# M203X.net
KiCad netlist of a schematic drawn in EAGLE
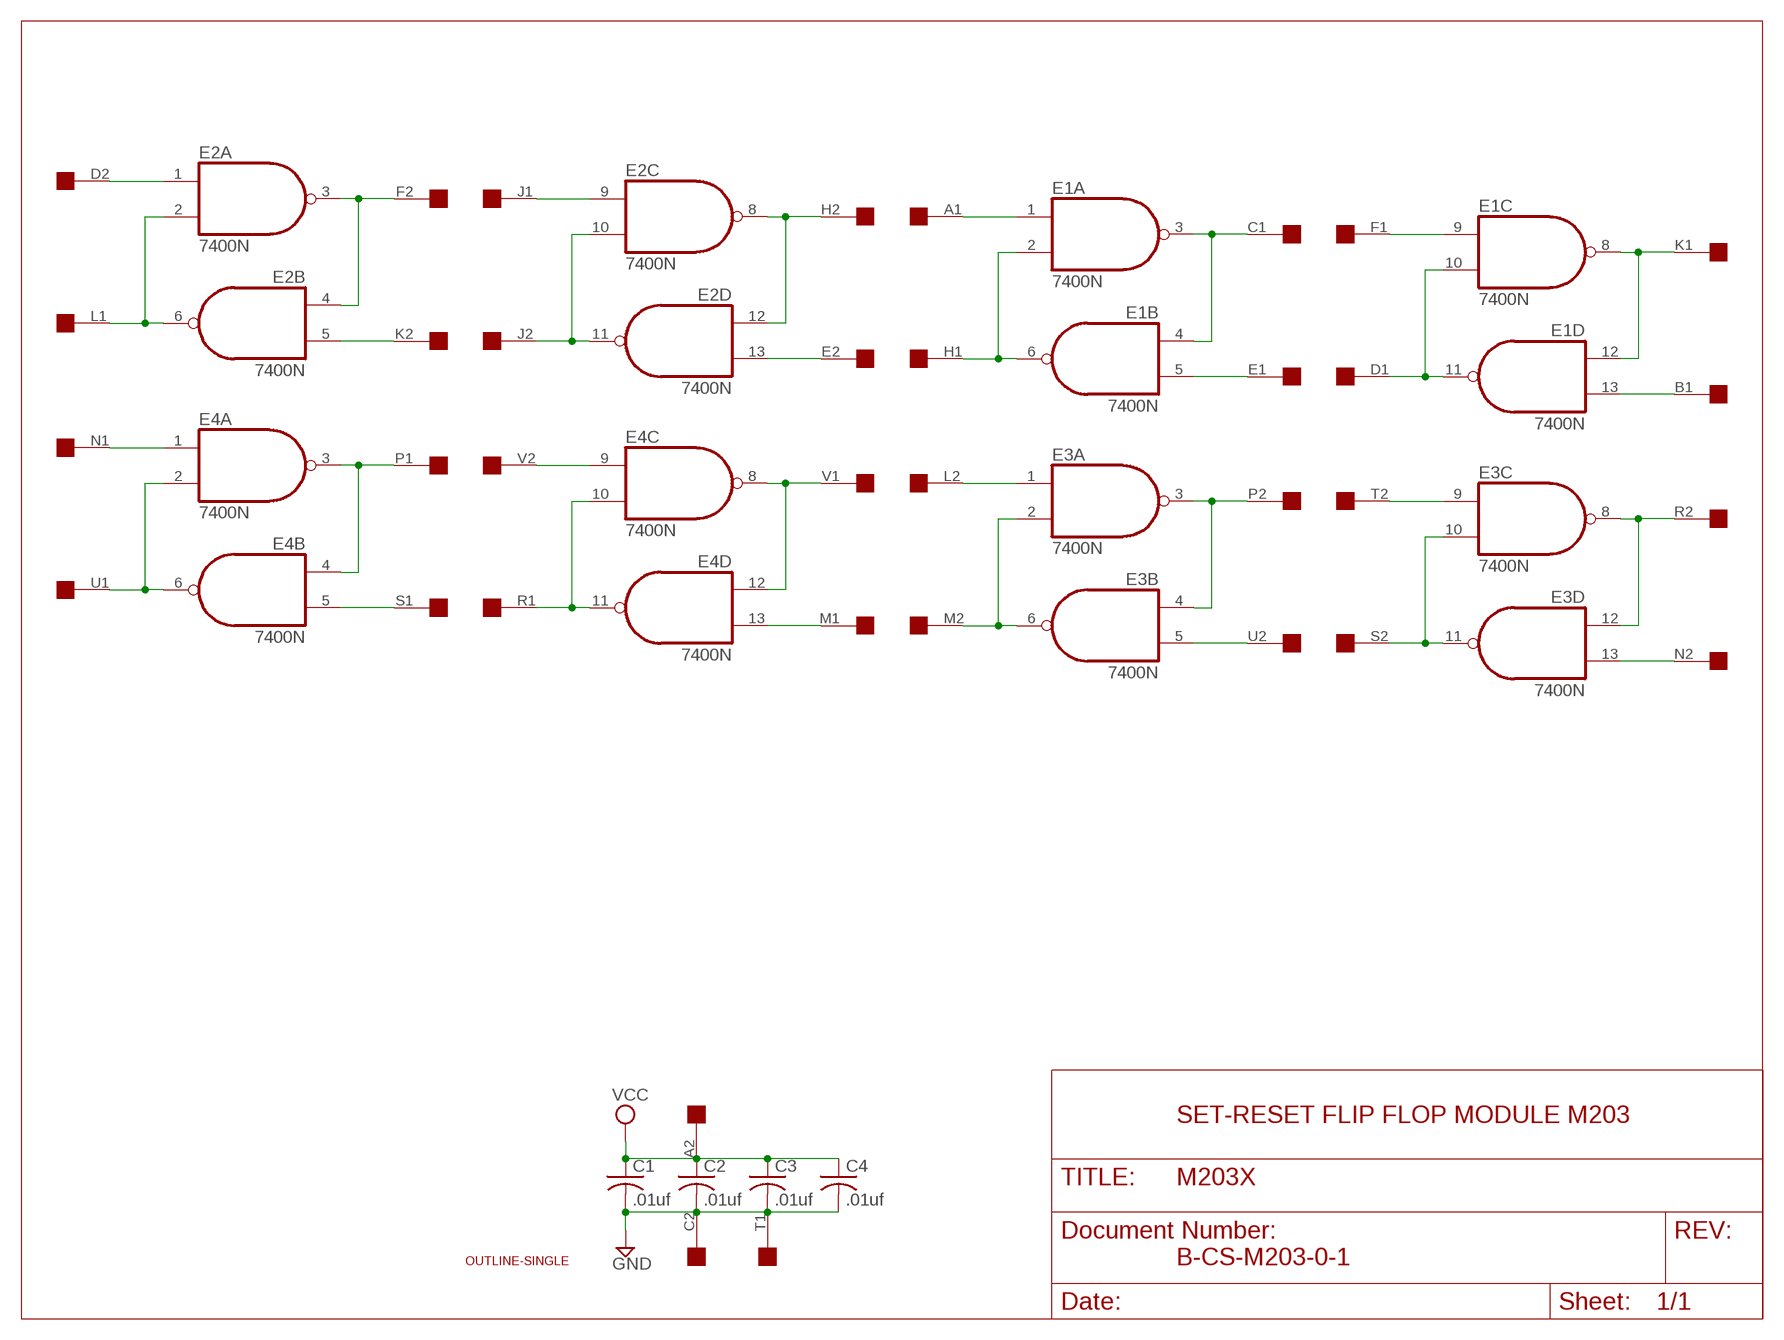
[diagram p0: schematic, sheet 1]

(export (version "E")
  (design (tool "Eeschema 10.0.6"))
  (components
    (comp (ref "C1")
      (value ".01uf")
      (footprint "eagle-import:C050-025X075")
      (libsource (lib "eagle-import") (part "C-US050-025X075"))
    )
    (comp (ref "C2")
      (value ".01uf")
      (footprint "eagle-import:C050-025X075")
      (libsource (lib "eagle-import") (part "C-US050-025X075"))
    )
    (comp (ref "C3")
      (value ".01uf")
      (footprint "eagle-import:C050-025X075")
      (libsource (lib "eagle-import") (part "C-US050-025X075"))
    )
    (comp (ref "C4")
      (value ".01uf")
      (footprint "eagle-import:C050-025X075")
      (libsource (lib "eagle-import") (part "C-US050-025X075"))
    )
    (comp (ref "E1")
      (value "7400N")
      (footprint "eagle-import:DIL14")
      (libsource (lib "eagle-import") (part "7400N"))
    )
    (comp (ref "E2")
      (value "7400N")
      (footprint "eagle-import:DIL14")
      (libsource (lib "eagle-import") (part "7400N"))
    )
    (comp (ref "E3")
      (value "7400N")
      (footprint "eagle-import:DIL14")
      (libsource (lib "eagle-import") (part "7400N"))
    )
    (comp (ref "E4")
      (value "7400N")
      (footprint "eagle-import:DIL14")
      (libsource (lib "eagle-import") (part "7400N"))
    )
    (comp (ref "U$1")
      (value "OUTLINE-SINGLE")
      (footprint "eagle-import:SINGLE")
      (libsource (lib "eagle-import") (part "OUTLINE-SINGLE"))
    )
    (comp (ref "U$2")
      (value "EDGE-2CONNECTOR")
      (footprint "eagle-import:EDGE-CON2")
      (libsource (lib "eagle-import") (part "EDGE-2CONNECTOR"))
    )
  )
  (nets
    (net (code "1") (name "GND") (class "Default")
      (node (ref "C1") (pin "2") (pinfunction "2_2") (pintype "passive"))
      (node (ref "C2") (pin "2") (pinfunction "2_2") (pintype "passive"))
      (node (ref "C3") (pin "2") (pinfunction "2_2") (pintype "passive"))
      (node (ref "C4") (pin "2") (pinfunction "2_2") (pintype "passive"))
      (node (ref "U$2") (pin "C2") (pinfunction "1_C2") (pintype "bidirectional"))
      (node (ref "U$2") (pin "T1") (pinfunction "1_T1") (pintype "bidirectional"))
    )
    (net (code "2") (name "Net-(E1A-I0)") (class "Default")
      (node (ref "E1") (pin "1") (pinfunction "I0_1") (pintype "input"))
      (node (ref "U$2") (pin "A1") (pinfunction "1_A1") (pintype "bidirectional"))
    )
    (net (code "3") (name "Net-(E1A-I1)") (class "Default")
      (node (ref "E1") (pin "2") (pinfunction "I1_2") (pintype "input"))
      (node (ref "E1") (pin "6") (pinfunction "O_6") (pintype "output"))
      (node (ref "U$2") (pin "H1") (pinfunction "1_H1") (pintype "bidirectional"))
    )
    (net (code "4") (name "Net-(E1A-O)") (class "Default")
      (node (ref "E1") (pin "3") (pinfunction "O_3") (pintype "output"))
      (node (ref "E1") (pin "4") (pinfunction "I0_4") (pintype "input"))
      (node (ref "U$2") (pin "C1") (pinfunction "1_C1") (pintype "bidirectional"))
    )
    (net (code "5") (name "Net-(E1B-I1)") (class "Default")
      (node (ref "E1") (pin "5") (pinfunction "I1_5") (pintype "input"))
      (node (ref "U$2") (pin "E1") (pinfunction "1_E1") (pintype "bidirectional"))
    )
    (net (code "6") (name "Net-(E1C-I0)") (class "Default")
      (node (ref "E1") (pin "9") (pinfunction "I0_9") (pintype "input"))
      (node (ref "U$2") (pin "F1") (pinfunction "1_F1") (pintype "bidirectional"))
    )
    (net (code "7") (name "Net-(E1C-I1)") (class "Default")
      (node (ref "E1") (pin "10") (pinfunction "I1_10") (pintype "input"))
      (node (ref "E1") (pin "11") (pinfunction "O_11") (pintype "output"))
      (node (ref "U$2") (pin "D1") (pinfunction "1_D1") (pintype "bidirectional"))
    )
    (net (code "8") (name "Net-(E1C-O)") (class "Default")
      (node (ref "E1") (pin "12") (pinfunction "I0_12") (pintype "input"))
      (node (ref "E1") (pin "8") (pinfunction "O_8") (pintype "output"))
      (node (ref "U$2") (pin "K1") (pinfunction "1_K1") (pintype "bidirectional"))
    )
    (net (code "9") (name "Net-(E1D-I1)") (class "Default")
      (node (ref "E1") (pin "13") (pinfunction "I1_13") (pintype "input"))
      (node (ref "U$2") (pin "B1") (pinfunction "1_B1") (pintype "bidirectional"))
    )
    (net (code "10") (name "Net-(E2A-I0)") (class "Default")
      (node (ref "E2") (pin "1") (pinfunction "I0_1") (pintype "input"))
      (node (ref "U$2") (pin "D2") (pinfunction "1_D2") (pintype "bidirectional"))
    )
    (net (code "11") (name "Net-(E2A-I1)") (class "Default")
      (node (ref "E2") (pin "2") (pinfunction "I1_2") (pintype "input"))
      (node (ref "E2") (pin "6") (pinfunction "O_6") (pintype "output"))
      (node (ref "U$2") (pin "L1") (pinfunction "1_L1") (pintype "bidirectional"))
    )
    (net (code "12") (name "Net-(E2A-O)") (class "Default")
      (node (ref "E2") (pin "3") (pinfunction "O_3") (pintype "output"))
      (node (ref "E2") (pin "4") (pinfunction "I0_4") (pintype "input"))
      (node (ref "U$2") (pin "F2") (pinfunction "1_F2") (pintype "bidirectional"))
    )
    (net (code "13") (name "Net-(E2B-I1)") (class "Default")
      (node (ref "E2") (pin "5") (pinfunction "I1_5") (pintype "input"))
      (node (ref "U$2") (pin "K2") (pinfunction "1_K2") (pintype "bidirectional"))
    )
    (net (code "14") (name "Net-(E2C-I0)") (class "Default")
      (node (ref "E2") (pin "9") (pinfunction "I0_9") (pintype "input"))
      (node (ref "U$2") (pin "J1") (pinfunction "1_J1") (pintype "bidirectional"))
    )
    (net (code "15") (name "Net-(E2C-I1)") (class "Default")
      (node (ref "E2") (pin "10") (pinfunction "I1_10") (pintype "input"))
      (node (ref "E2") (pin "11") (pinfunction "O_11") (pintype "output"))
      (node (ref "U$2") (pin "J2") (pinfunction "1_J2") (pintype "bidirectional"))
    )
    (net (code "16") (name "Net-(E2C-O)") (class "Default")
      (node (ref "E2") (pin "12") (pinfunction "I0_12") (pintype "input"))
      (node (ref "E2") (pin "8") (pinfunction "O_8") (pintype "output"))
      (node (ref "U$2") (pin "H2") (pinfunction "1_H2") (pintype "bidirectional"))
    )
    (net (code "17") (name "Net-(E2D-I1)") (class "Default")
      (node (ref "E2") (pin "13") (pinfunction "I1_13") (pintype "input"))
      (node (ref "U$2") (pin "E2") (pinfunction "1_E2") (pintype "bidirectional"))
    )
    (net (code "18") (name "Net-(E3A-I0)") (class "Default")
      (node (ref "E3") (pin "1") (pinfunction "I0_1") (pintype "input"))
      (node (ref "U$2") (pin "L2") (pinfunction "1_L2") (pintype "bidirectional"))
    )
    (net (code "19") (name "Net-(E3A-I1)") (class "Default")
      (node (ref "E3") (pin "2") (pinfunction "I1_2") (pintype "input"))
      (node (ref "E3") (pin "6") (pinfunction "O_6") (pintype "output"))
      (node (ref "U$2") (pin "M2") (pinfunction "1_M2") (pintype "bidirectional"))
    )
    (net (code "20") (name "Net-(E3A-O)") (class "Default")
      (node (ref "E3") (pin "3") (pinfunction "O_3") (pintype "output"))
      (node (ref "E3") (pin "4") (pinfunction "I0_4") (pintype "input"))
      (node (ref "U$2") (pin "P2") (pinfunction "1_P2") (pintype "bidirectional"))
    )
    (net (code "21") (name "Net-(E3B-I1)") (class "Default")
      (node (ref "E3") (pin "5") (pinfunction "I1_5") (pintype "input"))
      (node (ref "U$2") (pin "U2") (pinfunction "1_U2") (pintype "bidirectional"))
    )
    (net (code "22") (name "Net-(E3C-I0)") (class "Default")
      (node (ref "E3") (pin "9") (pinfunction "I0_9") (pintype "input"))
      (node (ref "U$2") (pin "T2") (pinfunction "1_T2") (pintype "bidirectional"))
    )
    (net (code "23") (name "Net-(E3C-I1)") (class "Default")
      (node (ref "E3") (pin "10") (pinfunction "I1_10") (pintype "input"))
      (node (ref "E3") (pin "11") (pinfunction "O_11") (pintype "output"))
      (node (ref "U$2") (pin "S2") (pinfunction "1_S2") (pintype "bidirectional"))
    )
    (net (code "24") (name "Net-(E3C-O)") (class "Default")
      (node (ref "E3") (pin "12") (pinfunction "I0_12") (pintype "input"))
      (node (ref "E3") (pin "8") (pinfunction "O_8") (pintype "output"))
      (node (ref "U$2") (pin "R2") (pinfunction "1_R2") (pintype "bidirectional"))
    )
    (net (code "25") (name "Net-(E3D-I1)") (class "Default")
      (node (ref "E3") (pin "13") (pinfunction "I1_13") (pintype "input"))
      (node (ref "U$2") (pin "N2") (pinfunction "1_N2") (pintype "bidirectional"))
    )
    (net (code "26") (name "Net-(E4A-I0)") (class "Default")
      (node (ref "E4") (pin "1") (pinfunction "I0_1") (pintype "input"))
      (node (ref "U$2") (pin "N1") (pinfunction "1_N1") (pintype "bidirectional"))
    )
    (net (code "27") (name "Net-(E4A-I1)") (class "Default")
      (node (ref "E4") (pin "2") (pinfunction "I1_2") (pintype "input"))
      (node (ref "E4") (pin "6") (pinfunction "O_6") (pintype "output"))
      (node (ref "U$2") (pin "U1") (pinfunction "1_U1") (pintype "bidirectional"))
    )
    (net (code "28") (name "Net-(E4A-O)") (class "Default")
      (node (ref "E4") (pin "3") (pinfunction "O_3") (pintype "output"))
      (node (ref "E4") (pin "4") (pinfunction "I0_4") (pintype "input"))
      (node (ref "U$2") (pin "P1") (pinfunction "1_P1") (pintype "bidirectional"))
    )
    (net (code "29") (name "Net-(E4B-I1)") (class "Default")
      (node (ref "E4") (pin "5") (pinfunction "I1_5") (pintype "input"))
      (node (ref "U$2") (pin "S1") (pinfunction "1_S1") (pintype "bidirectional"))
    )
    (net (code "30") (name "Net-(E4C-I0)") (class "Default")
      (node (ref "E4") (pin "9") (pinfunction "I0_9") (pintype "input"))
      (node (ref "U$2") (pin "V2") (pinfunction "1_V2") (pintype "bidirectional"))
    )
    (net (code "31") (name "Net-(E4C-I1)") (class "Default")
      (node (ref "E4") (pin "10") (pinfunction "I1_10") (pintype "input"))
      (node (ref "E4") (pin "11") (pinfunction "O_11") (pintype "output"))
      (node (ref "U$2") (pin "R1") (pinfunction "1_R1") (pintype "bidirectional"))
    )
    (net (code "32") (name "Net-(E4C-O)") (class "Default")
      (node (ref "E4") (pin "12") (pinfunction "I0_12") (pintype "input"))
      (node (ref "E4") (pin "8") (pinfunction "O_8") (pintype "output"))
      (node (ref "U$2") (pin "V1") (pinfunction "1_V1") (pintype "bidirectional"))
    )
    (net (code "33") (name "Net-(E4D-I1)") (class "Default")
      (node (ref "E4") (pin "13") (pinfunction "I1_13") (pintype "input"))
      (node (ref "U$2") (pin "M1") (pinfunction "1_M1") (pintype "bidirectional"))
    )
    (net (code "34") (name "VCC") (class "Default")
      (node (ref "C1") (pin "1") (pinfunction "1_1") (pintype "passive"))
      (node (ref "C2") (pin "1") (pinfunction "1_1") (pintype "passive"))
      (node (ref "C3") (pin "1") (pinfunction "1_1") (pintype "passive"))
      (node (ref "C4") (pin "1") (pinfunction "1_1") (pintype "passive"))
      (node (ref "U$2") (pin "A2") (pinfunction "1_A2") (pintype "bidirectional"))
    )
  )
)
